# MotorDriver.net
KiCad netlist of a schematic drawn in EAGLE
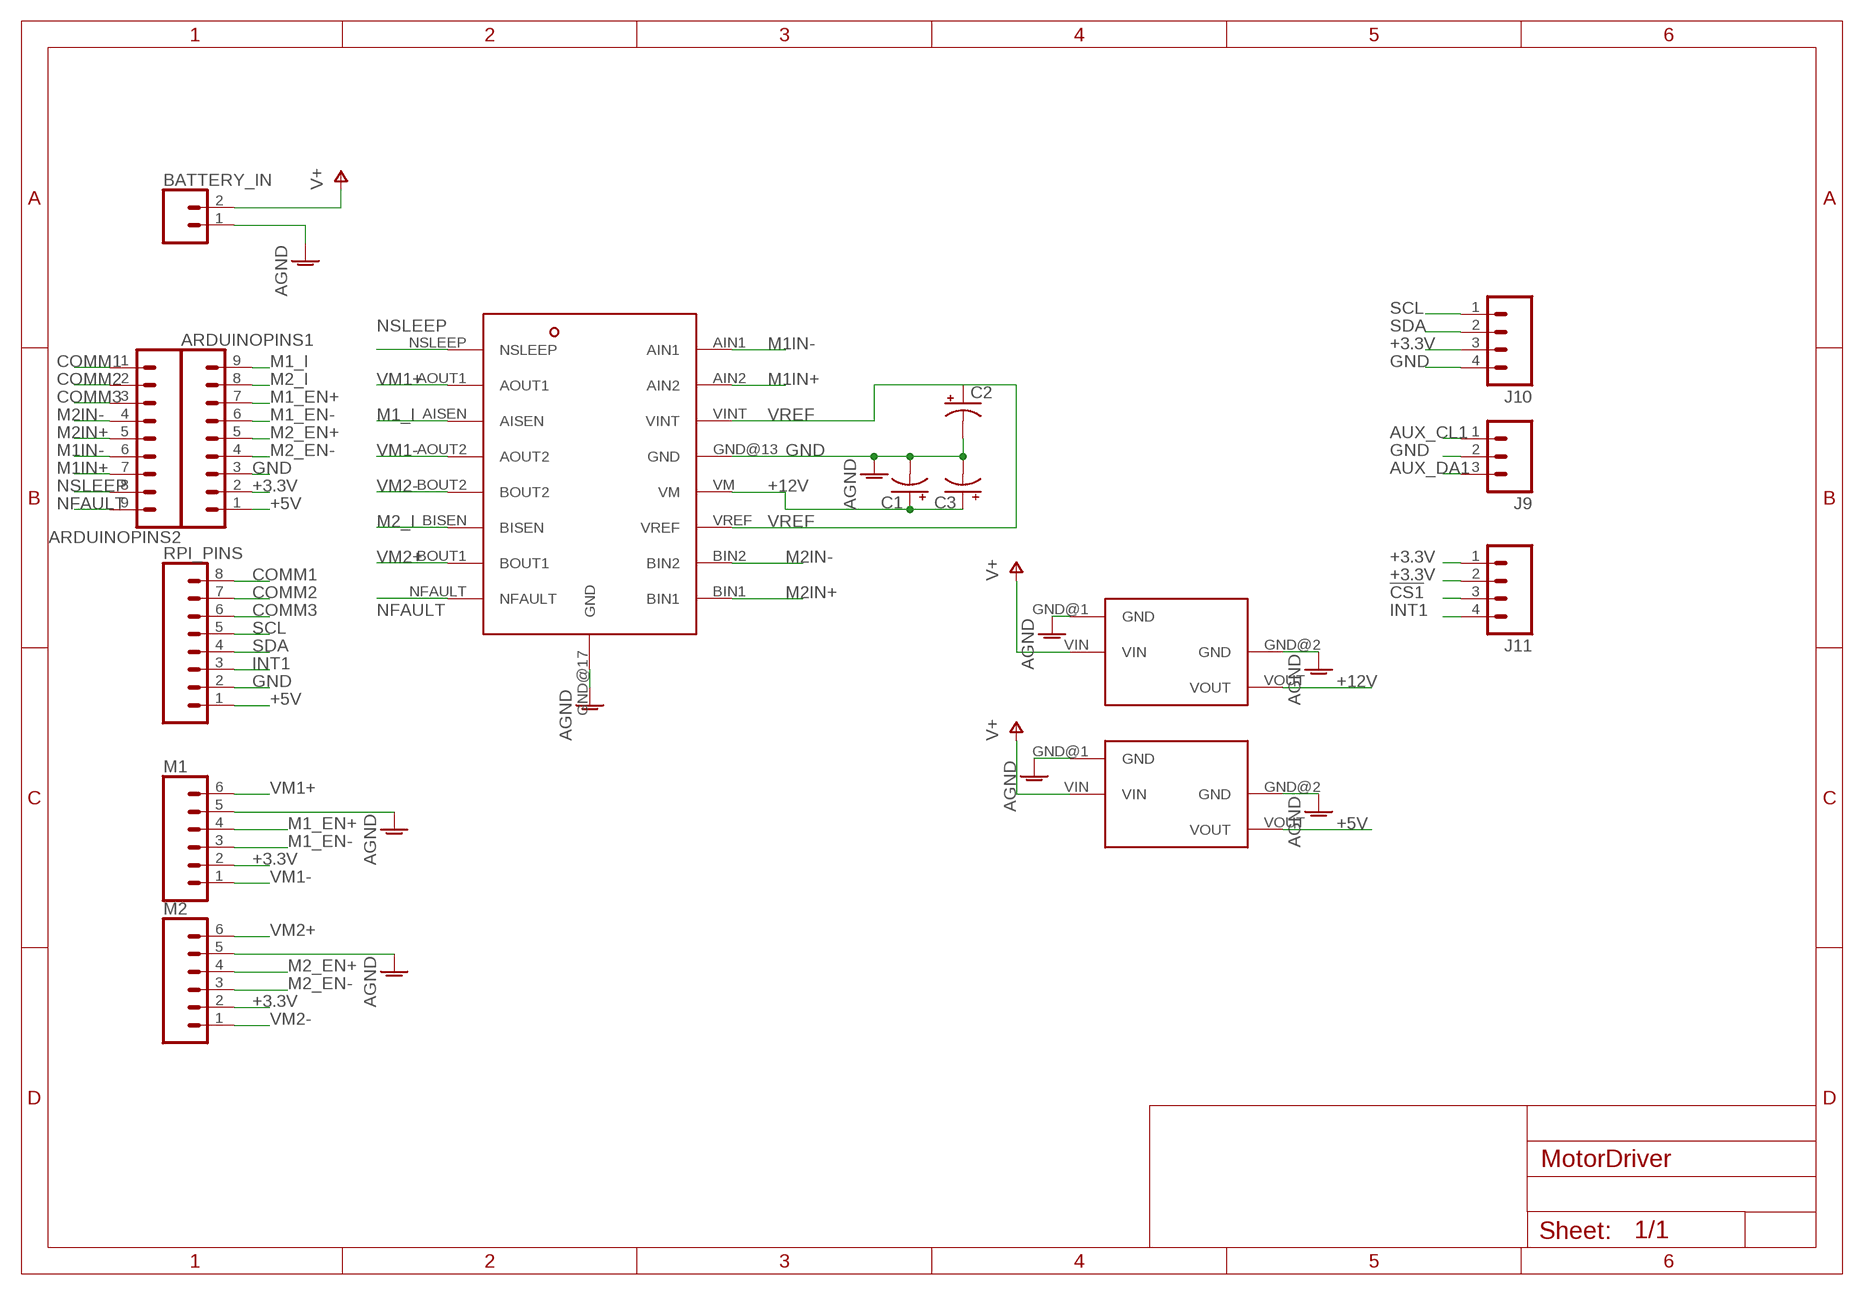
[diagram p0: schematic, sheet 1]

(export (version "E")
  (design (tool "Eeschema 10.0.6"))
  (components
    (comp (ref "ARDUINOPINS1")
      (value "CONN_09")
      (footprint "eagle-import:1X09")
      (libsource (lib "eagle-import") (part "CONN_09"))
    )
    (comp (ref "ARDUINOPINS2")
      (value "CONN_09")
      (footprint "eagle-import:1X09")
      (libsource (lib "eagle-import") (part "CONN_09"))
    )
    (comp (ref "BATTERY_IN")
      (value "CONN_02")
      (footprint "eagle-import:1X02")
      (libsource (lib "eagle-import") (part "CONN_02"))
    )
    (comp (ref "C1")
      (value "CPOL-USTT2D5")
      (footprint "eagle-import:TT2D5")
      (libsource (lib "eagle-import") (part "CPOL-USTT2D5"))
    )
    (comp (ref "C2")
      (value "CPOL-USTT2D5")
      (footprint "eagle-import:TT2D5")
      (libsource (lib "eagle-import") (part "CPOL-USTT2D5"))
    )
    (comp (ref "C3")
      (value "CPOL-USTT2D5")
      (footprint "eagle-import:TT2D5")
      (libsource (lib "eagle-import") (part "CPOL-USTT2D5"))
    )
    (comp (ref "HBRIDGE")
      (value "DRV8848")
      (footprint "eagle-import:DRV8848")
      (libsource (lib "eagle-import") (part "DRV8848"))
    )
    (comp (ref "J9")
      (value "M03PTH")
      (footprint "eagle-import:1X03")
      (libsource (lib "eagle-import") (part "M03PTH"))
    )
    (comp (ref "J10")
      (value "M04PTH")
      (footprint "eagle-import:1X04")
      (libsource (lib "eagle-import") (part "M04PTH"))
    )
    (comp (ref "J11")
      (value "M04PTH")
      (footprint "eagle-import:1X04")
      (libsource (lib "eagle-import") (part "M04PTH"))
    )
    (comp (ref "M1")
      (value "CONN_06SILK_FEMALE_PTH")
      (footprint "eagle-import:1X06")
      (libsource (lib "eagle-import") (part "CONN_06SILK_FEMALE_PTH"))
    )
    (comp (ref "M2")
      (value "CONN_06SILK_FEMALE_PTH")
      (footprint "eagle-import:1X06")
      (libsource (lib "eagle-import") (part "CONN_06SILK_FEMALE_PTH"))
    )
    (comp (ref "RPI_PINS")
      (value "CONN_08\"")
      (footprint "eagle-import:1X08")
      (libsource (lib "eagle-import") (part "CONN_08{dblquote}"))
    )
    (comp (ref "VREG_5V")
      (value "U3V50F12")
      (footprint "eagle-import:U3V50F12")
      (libsource (lib "eagle-import") (part "U3V50F12"))
    )
    (comp (ref "VREG_12V")
      (value "U3V50F12")
      (footprint "eagle-import:U3V50F12")
      (libsource (lib "eagle-import") (part "U3V50F12"))
    )
  )
  (nets
    (net (code "1") (name "/+3.3V") (class "Default")
      (node (ref "ARDUINOPINS1") (pin "2") (pinfunction "2_2") (pintype "passive"))
      (node (ref "J10") (pin "3") (pinfunction "3_3") (pintype "passive"))
      (node (ref "J11") (pin "1") (pinfunction "1_1") (pintype "passive"))
      (node (ref "J11") (pin "2") (pinfunction "2_2") (pintype "passive"))
      (node (ref "M1") (pin "2") (pinfunction "2_2") (pintype "passive"))
      (node (ref "M2") (pin "2") (pinfunction "2_2") (pintype "passive"))
    )
    (net (code "2") (name "/+5V") (class "Default")
      (node (ref "ARDUINOPINS1") (pin "1") (pinfunction "1_1") (pintype "passive"))
      (node (ref "RPI_PINS") (pin "1") (pinfunction "1_1") (pintype "passive"))
      (node (ref "VREG_5V") (pin "VOUT") (pinfunction "VOUT_VOUT") (pintype "bidirectional"))
    )
    (net (code "3") (name "/+12V") (class "Default")
      (node (ref "C1") (pin "+") (pinfunction "+_+") (pintype "passive"))
      (node (ref "C3") (pin "+") (pinfunction "+_+") (pintype "passive"))
      (node (ref "HBRIDGE") (pin "VM") (pinfunction "VM_VM") (pintype "bidirectional"))
      (node (ref "VREG_12V") (pin "VOUT") (pinfunction "VOUT_VOUT") (pintype "bidirectional"))
    )
    (net (code "4") (name "/AUX_CL1") (class "Default")
      (node (ref "J9") (pin "1") (pinfunction "1_1") (pintype "passive"))
    )
    (net (code "5") (name "/AUX_DA1") (class "Default")
      (node (ref "J9") (pin "3") (pinfunction "3_3") (pintype "passive"))
    )
    (net (code "6") (name "/COMM1") (class "Default")
      (node (ref "ARDUINOPINS2") (pin "1") (pinfunction "1_1") (pintype "passive"))
      (node (ref "RPI_PINS") (pin "8") (pinfunction "8_8") (pintype "passive"))
    )
    (net (code "7") (name "/COMM2") (class "Default")
      (node (ref "ARDUINOPINS2") (pin "2") (pinfunction "2_2") (pintype "passive"))
      (node (ref "RPI_PINS") (pin "7") (pinfunction "7_7") (pintype "passive"))
    )
    (net (code "8") (name "/COMM3") (class "Default")
      (node (ref "ARDUINOPINS2") (pin "3") (pinfunction "3_3") (pintype "passive"))
      (node (ref "RPI_PINS") (pin "6") (pinfunction "6_6") (pintype "passive"))
    )
    (net (code "9") (name "/INT1") (class "Default")
      (node (ref "J11") (pin "4") (pinfunction "4_4") (pintype "passive"))
      (node (ref "RPI_PINS") (pin "3") (pinfunction "3_3") (pintype "passive"))
    )
    (net (code "10") (name "/M1IN+") (class "Default")
      (node (ref "ARDUINOPINS2") (pin "7") (pinfunction "7_7") (pintype "passive"))
      (node (ref "HBRIDGE") (pin "AIN2") (pinfunction "AIN2_AIN2") (pintype "bidirectional"))
    )
    (net (code "11") (name "/M1IN-") (class "Default")
      (node (ref "ARDUINOPINS2") (pin "6") (pinfunction "6_6") (pintype "passive"))
      (node (ref "HBRIDGE") (pin "AIN1") (pinfunction "AIN1_AIN1") (pintype "bidirectional"))
    )
    (net (code "12") (name "/M1_EN+") (class "Default")
      (node (ref "ARDUINOPINS1") (pin "7") (pinfunction "7_7") (pintype "passive"))
      (node (ref "M1") (pin "4") (pinfunction "4_4") (pintype "passive"))
    )
    (net (code "13") (name "/M1_EN-") (class "Default")
      (node (ref "ARDUINOPINS1") (pin "6") (pinfunction "6_6") (pintype "passive"))
      (node (ref "M1") (pin "3") (pinfunction "3_3") (pintype "passive"))
    )
    (net (code "14") (name "/M1_I") (class "Default")
      (node (ref "ARDUINOPINS1") (pin "9") (pinfunction "9_9") (pintype "passive"))
      (node (ref "HBRIDGE") (pin "AISEN") (pinfunction "AISEN_AISEN") (pintype "bidirectional"))
    )
    (net (code "15") (name "/M2IN+") (class "Default")
      (node (ref "ARDUINOPINS2") (pin "5") (pinfunction "5_5") (pintype "passive"))
      (node (ref "HBRIDGE") (pin "BIN1") (pinfunction "BIN1_BIN1") (pintype "bidirectional"))
    )
    (net (code "16") (name "/M2IN-") (class "Default")
      (node (ref "ARDUINOPINS2") (pin "4") (pinfunction "4_4") (pintype "passive"))
      (node (ref "HBRIDGE") (pin "BIN2") (pinfunction "BIN2_BIN2") (pintype "bidirectional"))
    )
    (net (code "17") (name "/M2_EN+") (class "Default")
      (node (ref "ARDUINOPINS1") (pin "5") (pinfunction "5_5") (pintype "passive"))
      (node (ref "M2") (pin "4") (pinfunction "4_4") (pintype "passive"))
    )
    (net (code "18") (name "/M2_EN-") (class "Default")
      (node (ref "ARDUINOPINS1") (pin "4") (pinfunction "4_4") (pintype "passive"))
      (node (ref "M2") (pin "3") (pinfunction "3_3") (pintype "passive"))
    )
    (net (code "19") (name "/M2_I") (class "Default")
      (node (ref "ARDUINOPINS1") (pin "8") (pinfunction "8_8") (pintype "passive"))
      (node (ref "HBRIDGE") (pin "BISEN") (pinfunction "BISEN_BISEN") (pintype "bidirectional"))
    )
    (net (code "20") (name "/NFAULT") (class "Default")
      (node (ref "ARDUINOPINS2") (pin "9") (pinfunction "9_9") (pintype "passive"))
      (node (ref "HBRIDGE") (pin "NFAULT") (pinfunction "NFAULT_NFAULT") (pintype "bidirectional"))
    )
    (net (code "21") (name "/NSLEEP") (class "Default")
      (node (ref "ARDUINOPINS2") (pin "8") (pinfunction "8_8") (pintype "passive"))
      (node (ref "HBRIDGE") (pin "NSLEEP") (pinfunction "NSLEEP_NSLEEP") (pintype "bidirectional"))
    )
    (net (code "22") (name "/SCL") (class "Default")
      (node (ref "J10") (pin "1") (pinfunction "1_1") (pintype "passive"))
      (node (ref "RPI_PINS") (pin "5") (pinfunction "5_5") (pintype "passive"))
    )
    (net (code "23") (name "/SDA") (class "Default")
      (node (ref "J10") (pin "2") (pinfunction "2_2") (pintype "passive"))
      (node (ref "RPI_PINS") (pin "4") (pinfunction "4_4") (pintype "passive"))
    )
    (net (code "24") (name "/VM1+") (class "Default")
      (node (ref "HBRIDGE") (pin "AOUT1") (pinfunction "AOUT1_AOUT1") (pintype "bidirectional"))
      (node (ref "M1") (pin "6") (pinfunction "6_6") (pintype "passive"))
    )
    (net (code "25") (name "/VM1-") (class "Default")
      (node (ref "HBRIDGE") (pin "AOUT2") (pinfunction "AOUT2_AOUT2") (pintype "bidirectional"))
      (node (ref "M1") (pin "1") (pinfunction "1_1") (pintype "passive"))
    )
    (net (code "26") (name "/VM2+") (class "Default")
      (node (ref "HBRIDGE") (pin "BOUT1") (pinfunction "BOUT1_BOUT1") (pintype "bidirectional"))
      (node (ref "M2") (pin "6") (pinfunction "6_6") (pintype "passive"))
    )
    (net (code "27") (name "/VM2-") (class "Default")
      (node (ref "HBRIDGE") (pin "BOUT2") (pinfunction "BOUT2_BOUT2") (pintype "bidirectional"))
      (node (ref "M2") (pin "1") (pinfunction "1_1") (pintype "passive"))
    )
    (net (code "28") (name "/VREF") (class "Default")
      (node (ref "C2") (pin "+") (pinfunction "+_+") (pintype "passive"))
      (node (ref "HBRIDGE") (pin "VINT") (pinfunction "VINT_VINT") (pintype "bidirectional"))
      (node (ref "HBRIDGE") (pin "VREF") (pinfunction "VREF_VREF") (pintype "bidirectional"))
    )
    (net (code "29") (name "/~{CS1}") (class "Default")
      (node (ref "J11") (pin "3") (pinfunction "3_3") (pintype "passive"))
    )
    (net (code "30") (name "AGND") (class "Default")
      (node (ref "ARDUINOPINS1") (pin "3") (pinfunction "3_3") (pintype "passive"))
      (node (ref "BATTERY_IN") (pin "1") (pinfunction "1_1") (pintype "passive"))
      (node (ref "C1") (pin "-") (pinfunction "-_-") (pintype "passive"))
      (node (ref "C2") (pin "-") (pinfunction "-_-") (pintype "passive"))
      (node (ref "C3") (pin "-") (pinfunction "-_-") (pintype "passive"))
      (node (ref "HBRIDGE") (pin "GND@13") (pinfunction "GND_GND@13") (pintype "bidirectional"))
      (node (ref "HBRIDGE") (pin "GND@17") (pinfunction "GND_GND@17") (pintype "bidirectional"))
      (node (ref "J10") (pin "4") (pinfunction "4_4") (pintype "passive"))
      (node (ref "J9") (pin "2") (pinfunction "2_2") (pintype "passive"))
      (node (ref "M1") (pin "5") (pinfunction "5_5") (pintype "passive"))
      (node (ref "M2") (pin "5") (pinfunction "5_5") (pintype "passive"))
      (node (ref "RPI_PINS") (pin "2") (pinfunction "2_2") (pintype "passive"))
      (node (ref "VREG_12V") (pin "GND@1") (pinfunction "GND_GND@1") (pintype "bidirectional"))
      (node (ref "VREG_12V") (pin "GND@2") (pinfunction "GND_GND@2") (pintype "bidirectional"))
      (node (ref "VREG_5V") (pin "GND@1") (pinfunction "GND_GND@1") (pintype "bidirectional"))
      (node (ref "VREG_5V") (pin "GND@2") (pinfunction "GND_GND@2") (pintype "bidirectional"))
    )
    (net (code "31") (name "V+") (class "Default")
      (node (ref "BATTERY_IN") (pin "2") (pinfunction "2_2") (pintype "passive"))
      (node (ref "VREG_12V") (pin "VIN") (pinfunction "VIN_VIN") (pintype "bidirectional"))
      (node (ref "VREG_5V") (pin "VIN") (pinfunction "VIN_VIN") (pintype "bidirectional"))
    )
  )
)
